# GYRO_3-AXIS_-_ITG-3200.net
KiCad netlist of a schematic drawn in Altium Designer
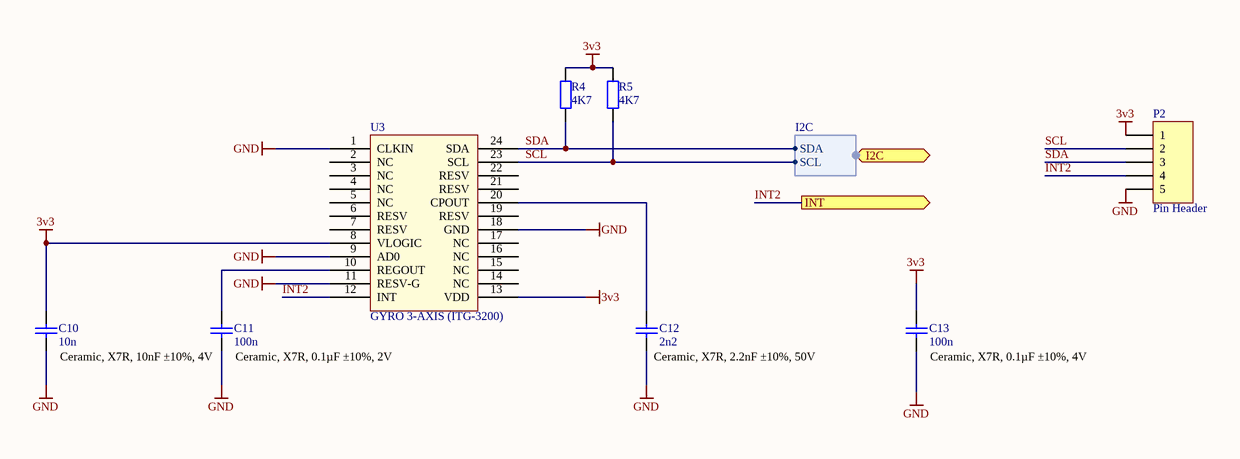
[diagram p0: GYRO 3-AXIS - ITG-3200.SchDoc]

(export (version "E")
  (design (tool "Eeschema 10.0.6"))
  (components
    (comp (ref "C10")
      (value "10n")
      (footprint "C0805")
      (fields (field (name "TOLERANCE") "0.1") (field (name "AUTHOR") "Willy Pietersz"))
      (libsource (lib "OurDb") (part "cap_NonPolar"))
    )
    (comp (ref "C11")
      (value "100n")
      (footprint "C0805")
      (fields (field (name "TOLERANCE") "0.1") (field (name "AUTHOR") "Willy Pietersz"))
      (libsource (lib "OurDb") (part "cap_NonPolar"))
    )
    (comp (ref "C12")
      (value "2n2")
      (footprint "C0805")
      (fields (field (name "TOLERANCE") "0.1") (field (name "AUTHOR") "Willy Pietersz"))
      (libsource (lib "OurDb") (part "cap_NonPolar"))
    )
    (comp (ref "C13")
      (value "100n")
      (footprint "C0805")
      (fields (field (name "TOLERANCE") "0.1") (field (name "AUTHOR") "Willy Pietersz"))
      (libsource (lib "OurDb") (part "cap_NonPolar"))
    )
    (comp (ref "P2")
      (value "Pin Header")
      (footprint "PH1x5_2.54")
      (description "Con1x5")
      (fields (field (name "PART NUMBER") "PH1x5") (field (name "AUTHOR") "Willy Pietersz"))
      (libsource (lib "OurDb") (part "Con1x5"))
    )
    (comp (ref "R4")
      (value "4K7")
      (footprint "R0805")
      (description "Resistor")
      (fields
        (field (name "POWER") "0.25W")
        (field (name "TOLERANCE") "0.05")
        (field (name "PUBLISHER") "Altium Limited")
        (field (name "AUTHOR") "Willy Pietersz")
      )
      (libsource (lib "OurDb") (part "RESISTOR"))
    )
    (comp (ref "R5")
      (value "4K7")
      (footprint "R0805")
      (description "Resistor")
      (fields
        (field (name "POWER") "0.25W")
        (field (name "TOLERANCE") "0.05")
        (field (name "PUBLISHER") "Altium Limited")
        (field (name "AUTHOR") "Willy Pietersz")
      )
      (libsource (lib "OurDb") (part "RESISTOR"))
    )
    (comp (ref "U3")
      (value "GYRO 3-AXIS (ITG-3200)")
      (footprint "QFN50P400X400-24V2M - GYRO 3axis")
      (description "Gyro, 3-axis")
      (fields (field (name "PART NUMBER") "ITG-3200"))
      (libsource (lib "OurDb") (part "ITG-3200"))
    )
  )
  (nets
    (net (code "2") (name "/INT2") (class "Default")
      (node (ref "P2") (pin "4") (pinfunction "4_4") (pintype "passive"))
      (node (ref "U3") (pin "12") (pinfunction "INT_12") (pintype "passive"))
    )
    (net (code "3") (name "/SCL") (class "Default")
      (node (ref "P2") (pin "2") (pinfunction "2_2") (pintype "passive"))
      (node (ref "R5") (pin "2") (pinfunction "2_2") (pintype "passive"))
      (node (ref "U3") (pin "23") (pinfunction "SCL_23") (pintype "passive"))
    )
    (net (code "4") (name "/SDA") (class "Default")
      (node (ref "P2") (pin "3") (pinfunction "3_3") (pintype "passive"))
      (node (ref "R4") (pin "2") (pinfunction "2_2") (pintype "passive"))
      (node (ref "U3") (pin "24") (pinfunction "SDA_24") (pintype "passive"))
    )
    (net (code "6") (name "3v3") (class "Default")
      (node (ref "C10") (pin "2") (pinfunction "2_2") (pintype "passive"))
      (node (ref "C13") (pin "2") (pinfunction "2_2") (pintype "passive"))
      (node (ref "P2") (pin "1") (pinfunction "1_1") (pintype "passive"))
      (node (ref "R4") (pin "1") (pinfunction "1_1") (pintype "passive"))
      (node (ref "R5") (pin "1") (pinfunction "1_1") (pintype "passive"))
      (node (ref "U3") (pin "13") (pinfunction "VDD_13") (pintype "passive"))
      (node (ref "U3") (pin "8") (pinfunction "VLOGIC_8") (pintype "passive"))
    )
    (net (code "7") (name "GND") (class "Default")
      (node (ref "C10") (pin "1") (pinfunction "1_1") (pintype "passive"))
      (node (ref "C11") (pin "1") (pinfunction "1_1") (pintype "passive"))
      (node (ref "C12") (pin "1") (pinfunction "1_1") (pintype "passive"))
      (node (ref "C13") (pin "1") (pinfunction "1_1") (pintype "passive"))
      (node (ref "P2") (pin "5") (pinfunction "5_5") (pintype "passive"))
      (node (ref "U3") (pin "1") (pinfunction "CLKIN_1") (pintype "passive"))
      (node (ref "U3") (pin "11") (pinfunction "RESV-G_11") (pintype "passive"))
      (node (ref "U3") (pin "18") (pinfunction "GND_18") (pintype "passive"))
      (node (ref "U3") (pin "9") (pinfunction "AD0_9") (pintype "passive"))
    )
    (net (code "8") (name "Net-(U3-CPOUT)") (class "Default")
      (node (ref "C12") (pin "2") (pinfunction "2_2") (pintype "passive"))
      (node (ref "U3") (pin "20") (pinfunction "CPOUT_20") (pintype "passive"))
    )
    (net (code "9") (name "Net-(U3-REGOUT)") (class "Default")
      (node (ref "C11") (pin "2") (pinfunction "2_2") (pintype "passive"))
      (node (ref "U3") (pin "10") (pinfunction "REGOUT_10") (pintype "passive"))
    )
    (net (code "10") (name "unconnected-(U3-NC-Pad2)") (class "Default")
      (node (ref "U3") (pin "2") (pinfunction "NC_2") (pintype "passive"))
    )
    (net (code "11") (name "unconnected-(U3-NC-Pad3)") (class "Default")
      (node (ref "U3") (pin "3") (pinfunction "NC_3") (pintype "passive"))
    )
    (net (code "12") (name "unconnected-(U3-NC-Pad4)") (class "Default")
      (node (ref "U3") (pin "4") (pinfunction "NC_4") (pintype "passive"))
    )
    (net (code "13") (name "unconnected-(U3-NC-Pad5)") (class "Default")
      (node (ref "U3") (pin "5") (pinfunction "NC_5") (pintype "passive"))
    )
    (net (code "14") (name "unconnected-(U3-NC-Pad14)") (class "Default")
      (node (ref "U3") (pin "14") (pinfunction "NC_14") (pintype "passive"))
    )
    (net (code "15") (name "unconnected-(U3-NC-Pad15)") (class "Default")
      (node (ref "U3") (pin "15") (pinfunction "NC_15") (pintype "passive"))
    )
    (net (code "16") (name "unconnected-(U3-NC-Pad16)") (class "Default")
      (node (ref "U3") (pin "16") (pinfunction "NC_16") (pintype "passive"))
    )
    (net (code "17") (name "unconnected-(U3-NC-Pad17)") (class "Default")
      (node (ref "U3") (pin "17") (pinfunction "NC_17") (pintype "passive"))
    )
    (net (code "18") (name "unconnected-(U3-RESV-Pad6)") (class "Default")
      (node (ref "U3") (pin "6") (pinfunction "RESV_6") (pintype "passive"))
    )
    (net (code "19") (name "unconnected-(U3-RESV-Pad7)") (class "Default")
      (node (ref "U3") (pin "7") (pinfunction "RESV_7") (pintype "passive"))
    )
    (net (code "20") (name "unconnected-(U3-RESV-Pad19)") (class "Default")
      (node (ref "U3") (pin "19") (pinfunction "RESV_19") (pintype "passive"))
    )
    (net (code "21") (name "unconnected-(U3-RESV-Pad21)") (class "Default")
      (node (ref "U3") (pin "21") (pinfunction "RESV_21") (pintype "passive"))
    )
    (net (code "22") (name "unconnected-(U3-RESV-Pad22)") (class "Default")
      (node (ref "U3") (pin "22") (pinfunction "RESV_22") (pintype "passive"))
    )
  )
)
